# Vsense_0-223_3V.net
KiCad netlist of a schematic drawn in Altium Designer
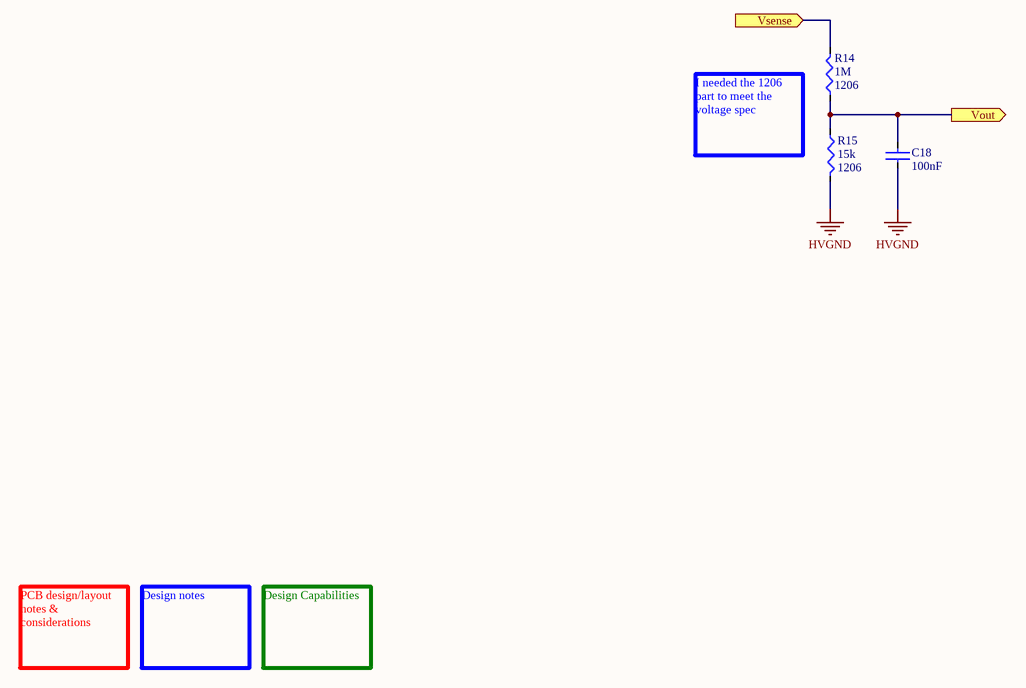
[diagram p0: Vsense 0-223.3V.SchDoc]

(export (version "E")
  (design (tool "Eeschema 10.0.6"))
  (components
    (comp (ref "C18")
      (value "100nF 0603 50V")
      (footprint "C0603 - Ceramic")
      (fields
        (field (name "MANUFACTURER") "Samsung Electro-Mechanics America, Inc")
        (field (name "MANUFACTURER PART NUMBER") "CL10B104KB8SFNC")
        (field (name "TOLERANCE") "±10%")
        (field (name "CAPACITANCE") "100nF")
      )
      (libsource (lib "Personal Library") (part "100nF 0603 50V"))
    )
    (comp (ref "R14")
      (value "1M 1206 1%")
      (footprint "R1210")
      (description "Resistor")
      (fields
        (field (name "MANUFACTURER") "Yageo")
        (field (name "MANUFACTURER PART NUMBER") "RV1206FR-071ML")
        (field (name "RESISTANCE (OHMS)") "1M")
        (field (name "SUPPLIER DEVICE PACKAGE") "1206")
      )
      (libsource (lib "Local Library") (part "1M 1206 1%"))
    )
    (comp (ref "R15")
      (value "Template - Resistor")
      (footprint "R1210")
      (fields
        (field (name "MANUFACTURER") "Yageo")
        (field (name "MANUFACTURER PART NUMBER") "RC1206FR-0715KL")
        (field (name "RESISTANCE (OHMS)") "15k")
        (field (name "TOLERANCE") "±1%")
        (field (name "SUPPLIER DEVICE PACKAGE") "1206")
      )
      (libsource (lib "Personal Library") (part "Template - Resistor"))
    )
  )
  (nets
    (net (code "1") (name "/Vout") (class "Default")
      (node (ref "C18") (pin "1") (pinfunction "1_1") (pintype "passive"))
      (node (ref "R14") (pin "2") (pinfunction "2_2") (pintype "passive"))
      (node (ref "R15") (pin "2") (pinfunction "2_2") (pintype "passive"))
    )
    (net (code "2") (name "/Vsense") (class "Default")
      (node (ref "R14") (pin "1") (pinfunction "1_1") (pintype "passive"))
    )
    (net (code "3") (name "HVGND") (class "Default")
      (node (ref "C18") (pin "2") (pinfunction "2_2") (pintype "passive"))
      (node (ref "R15") (pin "1") (pinfunction "1_1") (pintype "passive"))
    )
  )
)
